# LAUNCHXL-F28379D_5.net
KiCad netlist of a schematic drawn in Altium Designer
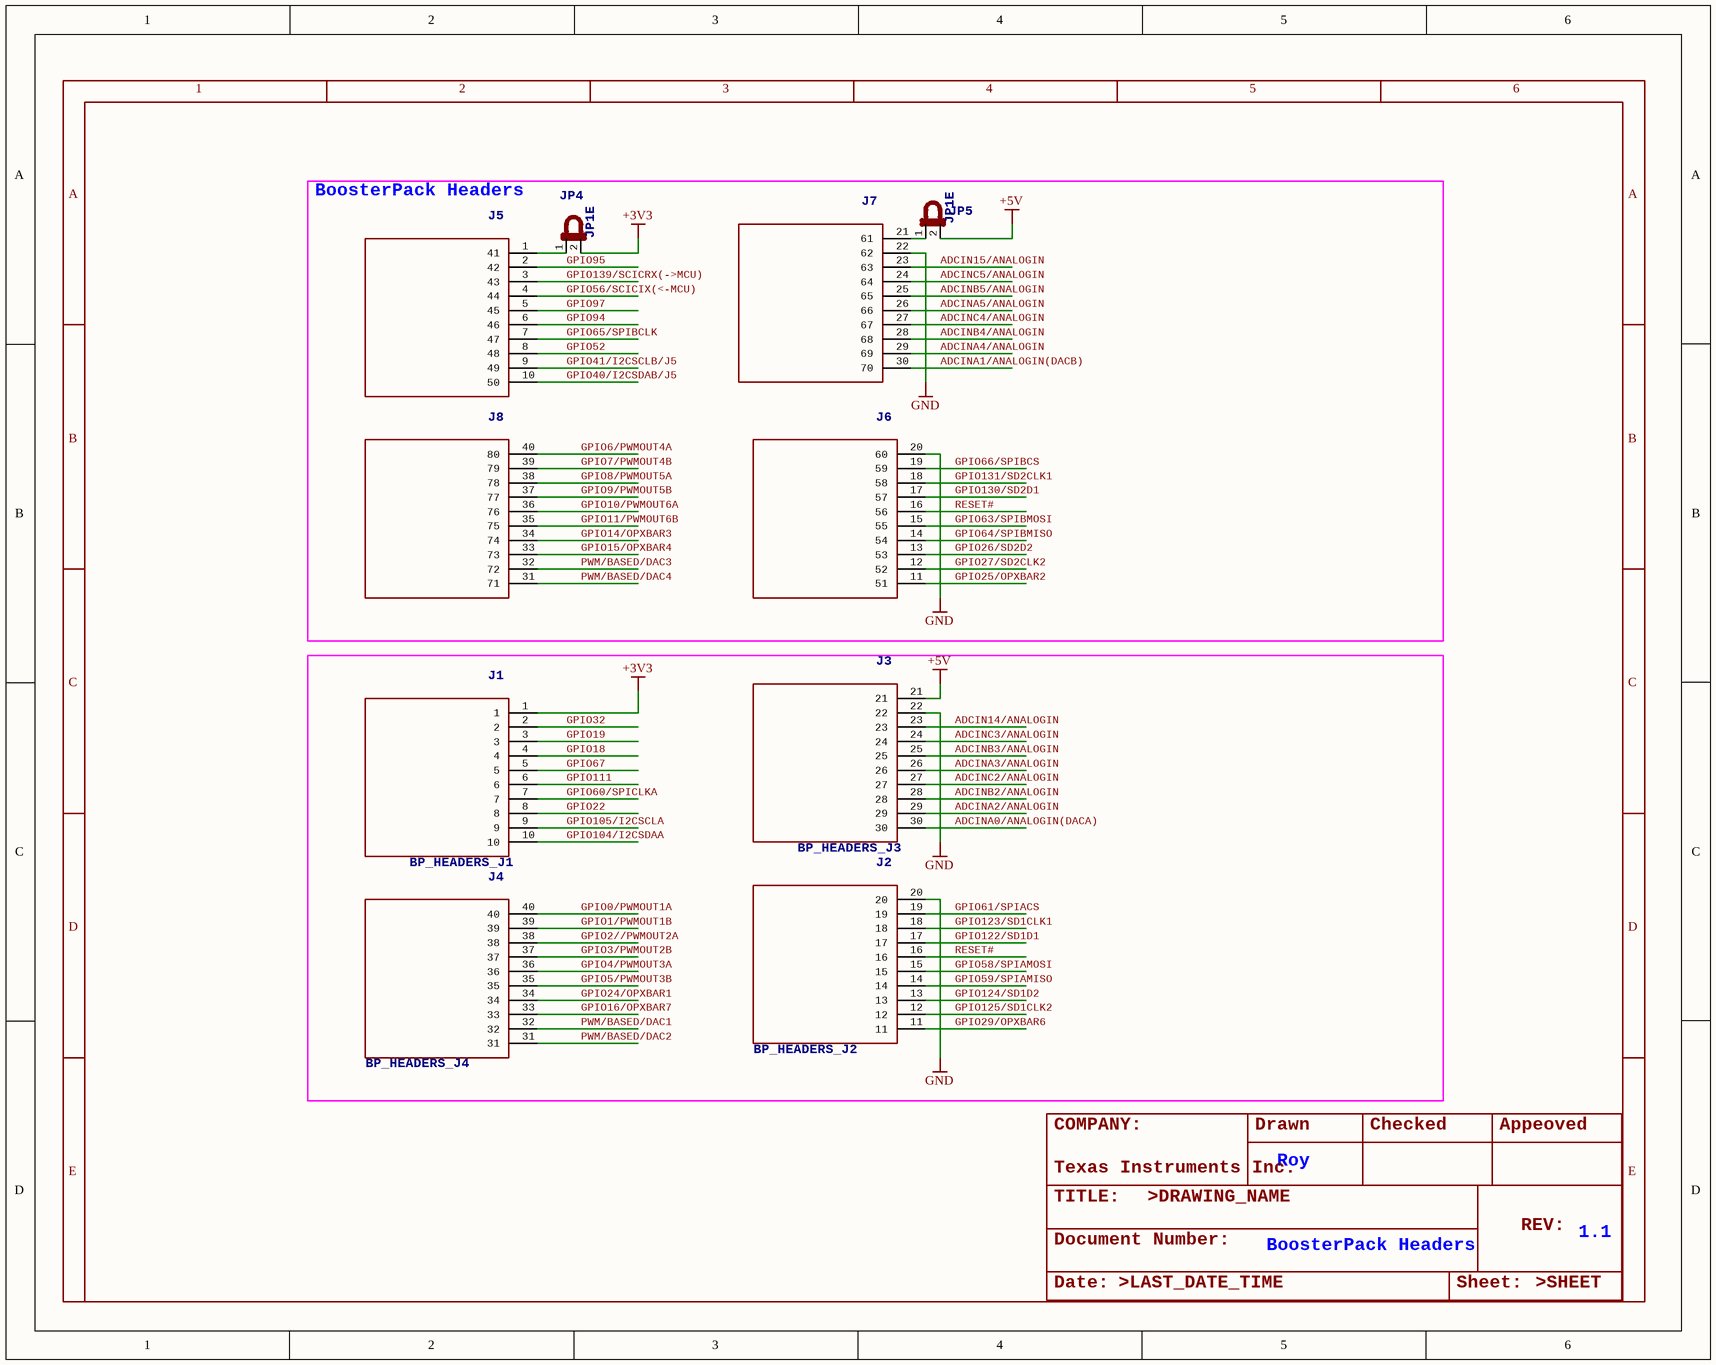
[diagram p0: LAUNCHXL-F28379D_5.SchDoc]

(export (version "E")
  (design (tool "Eeschema 10.0.6"))
  (components
    (comp (ref "J1")
      (value "BP_HEADERS_J1")
      (footprint "J1")
      (libsource (lib "LaunchPad_Template_Library") (part "BP_HEADERS_J1"))
    )
    (comp (ref "J2")
      (value "BP_HEADERS_J2")
      (footprint "J2")
      (libsource (lib "LaunchPad_Template_Library") (part "BP_HEADERS_J2"))
    )
    (comp (ref "J3")
      (value "BP_HEADERS_J3")
      (footprint "J3")
      (libsource (lib "LaunchPad_Template_Library") (part "BP_HEADERS_J3"))
    )
    (comp (ref "J4")
      (value "BP_HEADERS_J4")
      (footprint "J4")
      (libsource (lib "LaunchPad_Template_Library") (part "BP_HEADERS_J4"))
    )
    (comp (ref "J5")
      (value "LAUNCHPAD_TEMPLATE_LIBRARY_BP_HEADERS_J5")
      (footprint "LAUNCHPAD_TEMPLATE_LIBRARY_J5")
      (libsource (lib "LaunchPad_Template_Library") (part "LAUNCHPAD_TEMPLATE_LIBRARY_BP_HEADERS_J5"))
    )
    (comp (ref "J6")
      (value "LAUNCHPAD_TEMPLATE_LIBRARY_BP_HEADERS_J6")
      (footprint "LAUNCHPAD_TEMPLATE_LIBRARY_J6")
      (libsource (lib "LaunchPad_Template_Library") (part "LAUNCHPAD_TEMPLATE_LIBRARY_BP_HEADERS_J6"))
    )
    (comp (ref "J7")
      (value "LAUNCHPAD_TEMPLATE_LIBRARY_BP_HEADERS_J7")
      (footprint "LAUNCHPAD_TEMPLATE_LIBRARY_J7")
      (libsource (lib "LaunchPad_Template_Library") (part "LAUNCHPAD_TEMPLATE_LIBRARY_BP_HEADERS_J7"))
    )
    (comp (ref "J8")
      (value "LAUNCHPAD_TEMPLATE_LIBRARY_BP_HEADERS_J8")
      (footprint "LAUNCHPAD_TEMPLATE_LIBRARY_J8")
      (libsource (lib "LaunchPad_Template_Library") (part "LAUNCHPAD_TEMPLATE_LIBRARY_BP_HEADERS_J8"))
    )
    (comp (ref "JP4")
      (value "JP1E")
      (footprint "JP1")
      (description "<b>JUMPER</b>")
      (libsource (lib "jumper") (part "JP1E"))
    )
    (comp (ref "JP5")
      (value "JP1E")
      (footprint "JP1")
      (description "<b>JUMPER</b>")
      (libsource (lib "jumper") (part "JP1E"))
    )
    (comp (ref "U$12")
      (value "ROY_JUMPER")
      (footprint "ROY_JUMPER")
      (libsource (lib "roy") (part "ROY_JUMPER"))
    )
    (comp (ref "U$13")
      (value "ROY_JUMPER")
      (footprint "ROY_JUMPER")
      (libsource (lib "roy") (part "ROY_JUMPER"))
    )
  )
  (nets
    (net (code "1") (name "+3V3") (class "Default")
      (node (ref "J1") (pin "1") (pinfunction "1_1") (pintype "passive"))
      (node (ref "JP4") (pin "2") (pinfunction "2_2") (pintype "passive"))
    )
    (net (code "2") (name "+5V") (class "Default")
      (node (ref "J3") (pin "21") (pinfunction "21_21") (pintype "passive"))
      (node (ref "JP5") (pin "2") (pinfunction "2_2") (pintype "passive"))
    )
    (net (code "3") (name "/ADCIN14{slash}ANALOGIN") (class "Default")
      (node (ref "J3") (pin "23") (pinfunction "23_23") (pintype "passive"))
    )
    (net (code "4") (name "/ADCIN15{slash}ANALOGIN") (class "Default")
      (node (ref "J7") (pin "23") (pinfunction "63_23") (pintype "passive"))
    )
    (net (code "5") (name "/ADCINA0{slash}ANALOGIN(DACA)") (class "Default")
      (node (ref "J3") (pin "30") (pinfunction "30_30") (pintype "passive"))
    )
    (net (code "6") (name "/ADCINA1{slash}ANALOGIN(DACB)") (class "Default")
      (node (ref "J7") (pin "30") (pinfunction "70_30") (pintype "passive"))
    )
    (net (code "7") (name "/ADCINA2{slash}ANALOGIN") (class "Default")
      (node (ref "J3") (pin "29") (pinfunction "29_29") (pintype "passive"))
    )
    (net (code "8") (name "/ADCINA3{slash}ANALOGIN") (class "Default")
      (node (ref "J3") (pin "26") (pinfunction "26_26") (pintype "passive"))
    )
    (net (code "9") (name "/ADCINA4{slash}ANALOGIN") (class "Default")
      (node (ref "J7") (pin "29") (pinfunction "69_29") (pintype "passive"))
    )
    (net (code "10") (name "/ADCINA5{slash}ANALOGIN") (class "Default")
      (node (ref "J7") (pin "26") (pinfunction "66_26") (pintype "passive"))
    )
    (net (code "11") (name "/ADCINB2{slash}ANALOGIN") (class "Default")
      (node (ref "J3") (pin "28") (pinfunction "28_28") (pintype "passive"))
    )
    (net (code "12") (name "/ADCINB3{slash}ANALOGIN") (class "Default")
      (node (ref "J3") (pin "25") (pinfunction "25_25") (pintype "passive"))
    )
    (net (code "13") (name "/ADCINB4{slash}ANALOGIN") (class "Default")
      (node (ref "J7") (pin "28") (pinfunction "68_28") (pintype "passive"))
    )
    (net (code "14") (name "/ADCINB5{slash}ANALOGIN") (class "Default")
      (node (ref "J7") (pin "25") (pinfunction "65_25") (pintype "passive"))
    )
    (net (code "15") (name "/ADCINC2{slash}ANALOGIN") (class "Default")
      (node (ref "J3") (pin "27") (pinfunction "27_27") (pintype "passive"))
    )
    (net (code "16") (name "/ADCINC3{slash}ANALOGIN") (class "Default")
      (node (ref "J3") (pin "24") (pinfunction "24_24") (pintype "passive"))
    )
    (net (code "17") (name "/ADCINC4{slash}ANALOGIN") (class "Default")
      (node (ref "J7") (pin "27") (pinfunction "67_27") (pintype "passive"))
    )
    (net (code "18") (name "/ADCINC5{slash}ANALOGIN") (class "Default")
      (node (ref "J7") (pin "24") (pinfunction "64_24") (pintype "passive"))
    )
    (net (code "19") (name "/GPIO0{slash}PWMOUT1A") (class "Default")
      (node (ref "J4") (pin "40") (pinfunction "40_40") (pintype "passive"))
    )
    (net (code "20") (name "/GPIO1{slash}PWMOUT1B") (class "Default")
      (node (ref "J4") (pin "39") (pinfunction "39_39") (pintype "passive"))
    )
    (net (code "21") (name "/GPIO2{slash}{slash}PWMOUT2A") (class "Default")
      (node (ref "J4") (pin "38") (pinfunction "38_38") (pintype "passive"))
    )
    (net (code "22") (name "/GPIO3{slash}PWMOUT2B") (class "Default")
      (node (ref "J4") (pin "37") (pinfunction "37_37") (pintype "passive"))
    )
    (net (code "23") (name "/GPIO4{slash}PWMOUT3A") (class "Default")
      (node (ref "J4") (pin "36") (pinfunction "36_36") (pintype "passive"))
    )
    (net (code "24") (name "/GPIO5{slash}PWMOUT3B") (class "Default")
      (node (ref "J4") (pin "35") (pinfunction "35_35") (pintype "passive"))
    )
    (net (code "25") (name "/GPIO6{slash}PWMOUT4A") (class "Default")
      (node (ref "J8") (pin "40") (pinfunction "80_40") (pintype "passive"))
    )
    (net (code "26") (name "/GPIO7{slash}PWMOUT4B") (class "Default")
      (node (ref "J8") (pin "39") (pinfunction "79_39") (pintype "passive"))
    )
    (net (code "27") (name "/GPIO8{slash}PWMOUT5A") (class "Default")
      (node (ref "J8") (pin "38") (pinfunction "78_38") (pintype "passive"))
    )
    (net (code "28") (name "/GPIO9{slash}PWMOUT5B") (class "Default")
      (node (ref "J8") (pin "37") (pinfunction "77_37") (pintype "passive"))
    )
    (net (code "29") (name "/GPIO10{slash}PWMOUT6A") (class "Default")
      (node (ref "J8") (pin "36") (pinfunction "76_36") (pintype "passive"))
    )
    (net (code "30") (name "/GPIO11{slash}PWMOUT6B") (class "Default")
      (node (ref "J8") (pin "35") (pinfunction "75_35") (pintype "passive"))
    )
    (net (code "31") (name "/GPIO14{slash}OPXBAR3") (class "Default")
      (node (ref "J8") (pin "34") (pinfunction "74_34") (pintype "passive"))
    )
    (net (code "32") (name "/GPIO15{slash}OPXBAR4") (class "Default")
      (node (ref "J8") (pin "33") (pinfunction "73_33") (pintype "passive"))
    )
    (net (code "33") (name "/GPIO16{slash}OPXBAR7") (class "Default")
      (node (ref "J4") (pin "33") (pinfunction "33_33") (pintype "passive"))
    )
    (net (code "34") (name "/GPIO18") (class "Default")
      (node (ref "J1") (pin "4") (pinfunction "4_4") (pintype "passive"))
    )
    (net (code "35") (name "/GPIO19") (class "Default")
      (node (ref "J1") (pin "3") (pinfunction "3_3") (pintype "passive"))
    )
    (net (code "36") (name "/GPIO22") (class "Default")
      (node (ref "J1") (pin "8") (pinfunction "8_8") (pintype "passive"))
    )
    (net (code "37") (name "/GPIO24{slash}OPXBAR1") (class "Default")
      (node (ref "J4") (pin "34") (pinfunction "34_34") (pintype "passive"))
    )
    (net (code "38") (name "/GPIO25{slash}OPXBAR2") (class "Default")
      (node (ref "J6") (pin "11") (pinfunction "51_11") (pintype "passive"))
    )
    (net (code "39") (name "/GPIO26{slash}SD2D2") (class "Default")
      (node (ref "J6") (pin "13") (pinfunction "53_13") (pintype "passive"))
    )
    (net (code "40") (name "/GPIO27{slash}SD2CLK2") (class "Default")
      (node (ref "J6") (pin "12") (pinfunction "52_12") (pintype "passive"))
    )
    (net (code "41") (name "/GPIO29{slash}OPXBAR6") (class "Default")
      (node (ref "J2") (pin "11") (pinfunction "11_11") (pintype "passive"))
    )
    (net (code "42") (name "/GPIO32") (class "Default")
      (node (ref "J1") (pin "2") (pinfunction "2_2") (pintype "passive"))
    )
    (net (code "43") (name "/GPIO40{slash}I2CSDAB{slash}J5") (class "Default")
      (node (ref "J5") (pin "10") (pinfunction "50_10") (pintype "passive"))
    )
    (net (code "44") (name "/GPIO41{slash}I2CSCLB{slash}J5") (class "Default")
      (node (ref "J5") (pin "9") (pinfunction "49_9") (pintype "passive"))
    )
    (net (code "45") (name "/GPIO52") (class "Default")
      (node (ref "J5") (pin "8") (pinfunction "48_8") (pintype "passive"))
    )
    (net (code "46") (name "/GPIO56{slash}SCICIX(<-MCU)") (class "Default")
      (node (ref "J5") (pin "4") (pinfunction "44_4") (pintype "passive"))
    )
    (net (code "47") (name "/GPIO58{slash}SPIAMOSI") (class "Default")
      (node (ref "J2") (pin "15") (pinfunction "15_15") (pintype "passive"))
    )
    (net (code "48") (name "/GPIO59{slash}SPIAMISO") (class "Default")
      (node (ref "J2") (pin "14") (pinfunction "14_14") (pintype "passive"))
    )
    (net (code "49") (name "/GPIO60{slash}SPICLKA") (class "Default")
      (node (ref "J1") (pin "7") (pinfunction "7_7") (pintype "passive"))
    )
    (net (code "50") (name "/GPIO61{slash}SPIACS") (class "Default")
      (node (ref "J2") (pin "19") (pinfunction "19_19") (pintype "passive"))
    )
    (net (code "51") (name "/GPIO63{slash}SPIBMOSI") (class "Default")
      (node (ref "J6") (pin "15") (pinfunction "55_15") (pintype "passive"))
    )
    (net (code "52") (name "/GPIO64{slash}SPIBMISO") (class "Default")
      (node (ref "J6") (pin "14") (pinfunction "54_14") (pintype "passive"))
    )
    (net (code "53") (name "/GPIO65{slash}SPIBCLK") (class "Default")
      (node (ref "J5") (pin "7") (pinfunction "47_7") (pintype "passive"))
    )
    (net (code "54") (name "/GPIO66{slash}SPIBCS") (class "Default")
      (node (ref "J6") (pin "19") (pinfunction "59_19") (pintype "passive"))
    )
    (net (code "55") (name "/GPIO67") (class "Default")
      (node (ref "J1") (pin "5") (pinfunction "5_5") (pintype "passive"))
    )
    (net (code "56") (name "/GPIO94") (class "Default")
      (node (ref "J5") (pin "6") (pinfunction "46_6") (pintype "passive"))
    )
    (net (code "57") (name "/GPIO95") (class "Default")
      (node (ref "J5") (pin "2") (pinfunction "42_2") (pintype "passive"))
    )
    (net (code "58") (name "/GPIO97") (class "Default")
      (node (ref "J5") (pin "5") (pinfunction "45_5") (pintype "passive"))
    )
    (net (code "59") (name "/GPIO104{slash}I2CSDAA") (class "Default")
      (node (ref "J1") (pin "10") (pinfunction "10_10") (pintype "passive"))
    )
    (net (code "60") (name "/GPIO105{slash}I2CSCLA") (class "Default")
      (node (ref "J1") (pin "9") (pinfunction "9_9") (pintype "passive"))
    )
    (net (code "61") (name "/GPIO111") (class "Default")
      (node (ref "J1") (pin "6") (pinfunction "6_6") (pintype "passive"))
    )
    (net (code "62") (name "/GPIO122{slash}SD1D1") (class "Default")
      (node (ref "J2") (pin "17") (pinfunction "17_17") (pintype "passive"))
    )
    (net (code "63") (name "/GPIO123{slash}SD1CLK1") (class "Default")
      (node (ref "J2") (pin "18") (pinfunction "18_18") (pintype "passive"))
    )
    (net (code "64") (name "/GPIO124{slash}SD1D2") (class "Default")
      (node (ref "J2") (pin "13") (pinfunction "13_13") (pintype "passive"))
    )
    (net (code "65") (name "/GPIO125{slash}SD1CLK2") (class "Default")
      (node (ref "J2") (pin "12") (pinfunction "12_12") (pintype "passive"))
    )
    (net (code "66") (name "/GPIO130{slash}SD2D1") (class "Default")
      (node (ref "J6") (pin "17") (pinfunction "57_17") (pintype "passive"))
    )
    (net (code "67") (name "/GPIO131{slash}SD2CLK1") (class "Default")
      (node (ref "J6") (pin "18") (pinfunction "58_18") (pintype "passive"))
    )
    (net (code "68") (name "/GPIO139{slash}SCICRX(->MCU)") (class "Default")
      (node (ref "J5") (pin "3") (pinfunction "43_3") (pintype "passive"))
    )
    (net (code "69") (name "/PWM{slash}BASED{slash}DAC1") (class "Default")
      (node (ref "J4") (pin "32") (pinfunction "32_32") (pintype "passive"))
    )
    (net (code "70") (name "/PWM{slash}BASED{slash}DAC2") (class "Default")
      (node (ref "J4") (pin "31") (pinfunction "31_31") (pintype "passive"))
    )
    (net (code "71") (name "/PWM{slash}BASED{slash}DAC3") (class "Default")
      (node (ref "J8") (pin "32") (pinfunction "72_32") (pintype "passive"))
    )
    (net (code "72") (name "/PWM{slash}BASED{slash}DAC4") (class "Default")
      (node (ref "J8") (pin "31") (pinfunction "71_31") (pintype "passive"))
    )
    (net (code "73") (name "/RESET#") (class "Default")
      (node (ref "J2") (pin "16") (pinfunction "16_16") (pintype "passive"))
      (node (ref "J6") (pin "16") (pinfunction "56_16") (pintype "passive"))
    )
    (net (code "74") (name "GND") (class "Default")
      (node (ref "J2") (pin "20") (pinfunction "20_20") (pintype "passive"))
      (node (ref "J3") (pin "22") (pinfunction "22_22") (pintype "passive"))
      (node (ref "J6") (pin "20") (pinfunction "60_20") (pintype "passive"))
      (node (ref "J7") (pin "22") (pinfunction "62_22") (pintype "passive"))
    )
    (net (code "75") (name "Net-(J5-41)") (class "Default")
      (node (ref "J5") (pin "1") (pinfunction "41_1") (pintype "passive"))
      (node (ref "JP4") (pin "1") (pinfunction "1_1") (pintype "passive"))
    )
    (net (code "76") (name "Net-(J7-61)") (class "Default")
      (node (ref "J7") (pin "21") (pinfunction "61_21") (pintype "passive"))
      (node (ref "JP5") (pin "1") (pinfunction "1_1") (pintype "passive"))
    )
  )
)
